# monoblink_wifi_v2.net
KiCad netlist of a schematic drawn in EAGLE
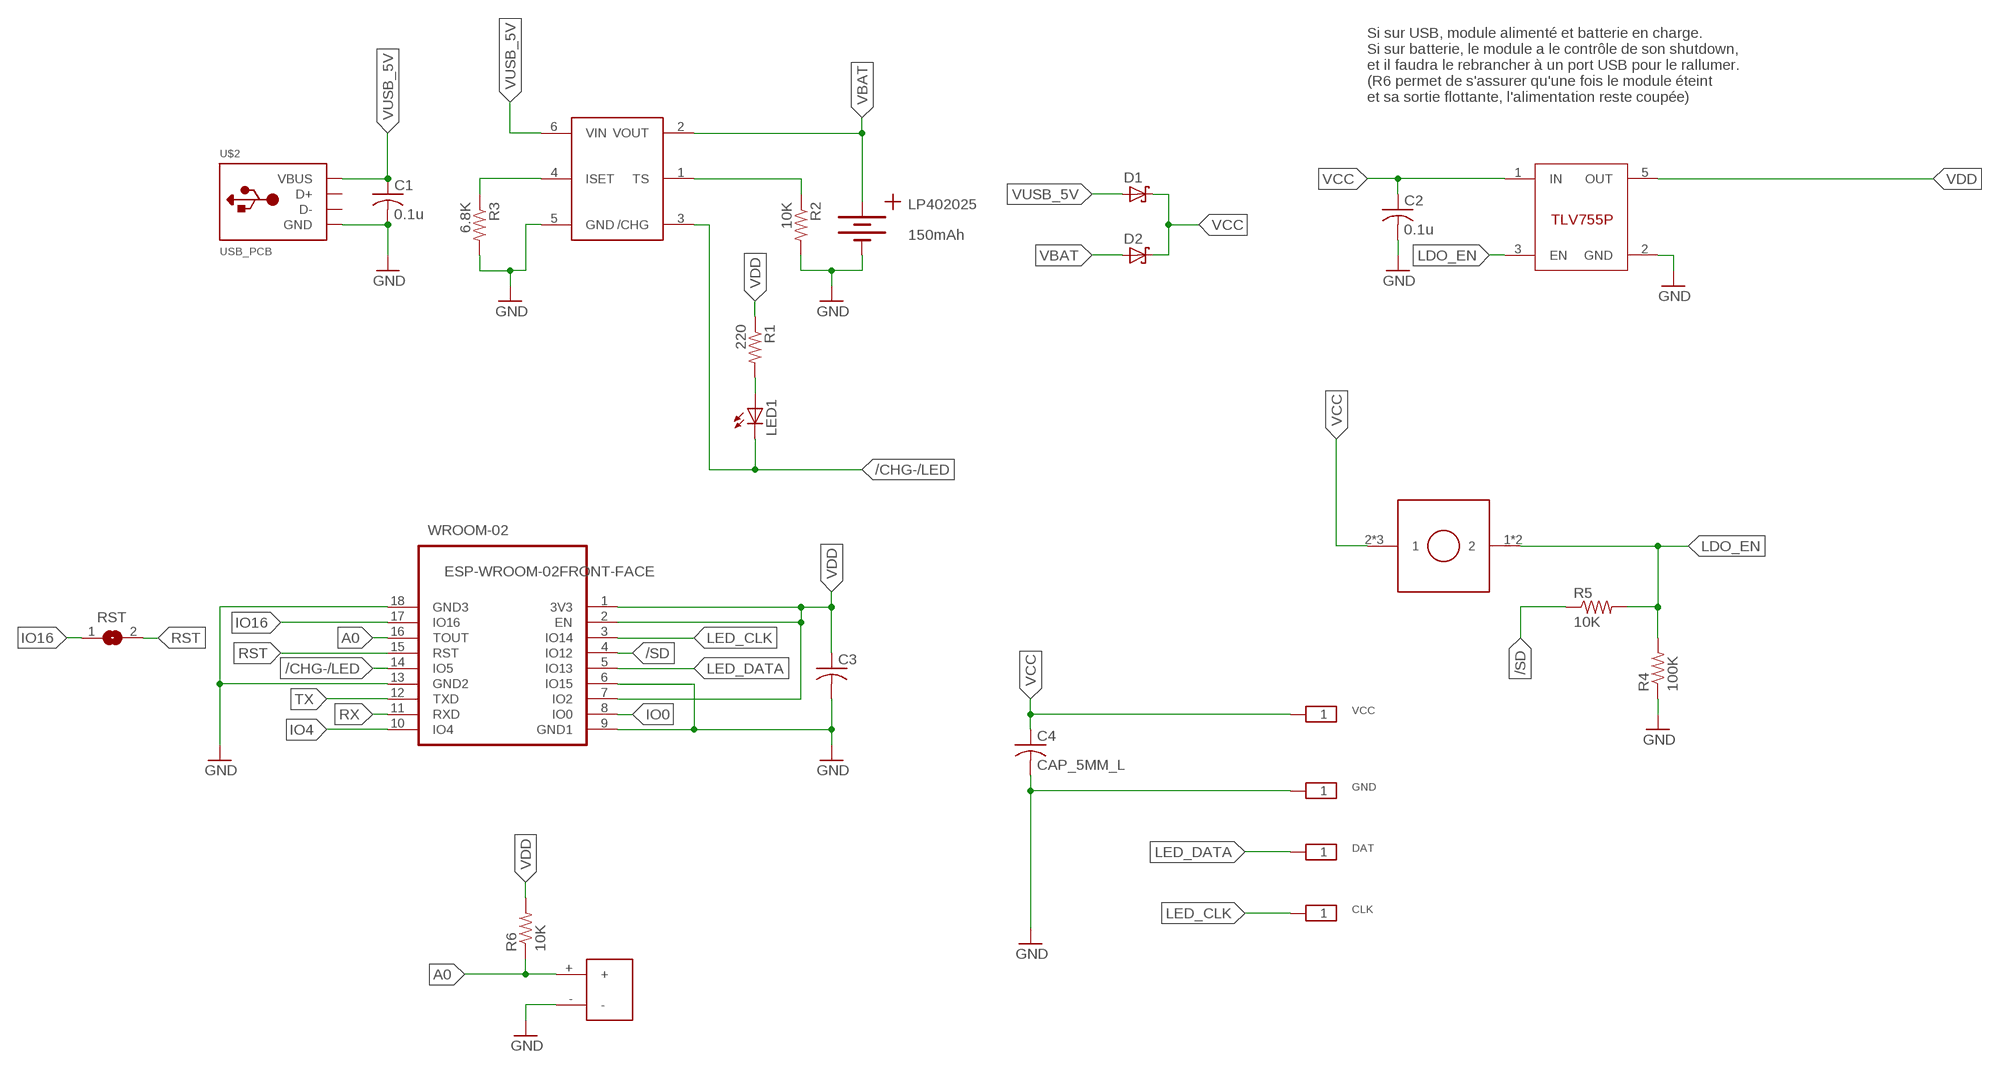
[diagram p0: schematic, sheet 1]

(export (version "E")
  (design (tool "Eeschema 10.0.6"))
  (components
    (comp (ref "C1")
      (value "0.1u")
      (footprint "eagle-import:C0603")
      (libsource (lib "eagle-import") (part "C-USC0603"))
    )
    (comp (ref "C2")
      (value "0.1u")
      (footprint "eagle-import:C0603")
      (libsource (lib "eagle-import") (part "C-USC0603"))
    )
    (comp (ref "C3")
      (value "C-USC0603")
      (footprint "eagle-import:C0603")
      (libsource (lib "eagle-import") (part "C-USC0603"))
    )
    (comp (ref "C4")
      (value "CAP_5MM_L")
      (footprint "eagle-import:TT2D5L")
      (libsource (lib "eagle-import") (part "CAP_5MM_L"))
    )
    (comp (ref "CHG")
      (value "BQ21040")
      (footprint "eagle-import:SOT23-6")
      (libsource (lib "eagle-import") (part "BQ21040"))
    )
    (comp (ref "CLK")
      (value "TESTPAD_PROGSPRING_PIN")
      (footprint "eagle-import:MATRIX_CONN")
      (libsource (lib "eagle-import") (part "TESTPAD_PROGSPRING_PIN"))
    )
    (comp (ref "D1")
      (value "NSR0320MW2T1G")
      (footprint "eagle-import:SOD323")
      (libsource (lib "eagle-import") (part "NSR0320MW2T1G"))
    )
    (comp (ref "D2")
      (value "NSR0320MW2T1G")
      (footprint "eagle-import:SOD323")
      (libsource (lib "eagle-import") (part "NSR0320MW2T1G"))
    )
    (comp (ref "DAT")
      (value "TESTPAD_PROGSPRING_PIN")
      (footprint "eagle-import:MATRIX_CONN")
      (libsource (lib "eagle-import") (part "TESTPAD_PROGSPRING_PIN"))
    )
    (comp (ref "GND")
      (value "TESTPAD_PROGSPRING_PIN")
      (footprint "eagle-import:MATRIX_CONN")
      (libsource (lib "eagle-import") (part "TESTPAD_PROGSPRING_PIN"))
    )
    (comp (ref "LDO")
      (value "TLV755P")
      (footprint "eagle-import:SOT23-5")
      (libsource (lib "eagle-import") (part "TLV755P"))
    )
    (comp (ref "LED1")
      (value "LEDCHIP-LED0603")
      (footprint "eagle-import:CHIP-LED0603")
      (libsource (lib "eagle-import") (part "LEDCHIP-LED0603"))
    )
    (comp (ref "LP402025")
      (value "150mAh")
      (footprint "eagle-import:BATT_CON")
      (libsource (lib "eagle-import") (part "BATT"))
    )
    (comp (ref "ON/OFF")
      (value "KMS231GPLFSNO_PEGS")
      (footprint "eagle-import:KMS231GLFS")
      (libsource (lib "eagle-import") (part "KMS231GPLFSNO_PEGS"))
    )
    (comp (ref "R1")
      (value "220")
      (footprint "eagle-import:R0603")
      (libsource (lib "eagle-import") (part "R-US_R0603"))
    )
    (comp (ref "R2")
      (value "10K")
      (footprint "eagle-import:R0603")
      (libsource (lib "eagle-import") (part "R-US_R0603"))
    )
    (comp (ref "R3")
      (value "6.8K")
      (footprint "eagle-import:R0603")
      (libsource (lib "eagle-import") (part "R-US_R0603"))
    )
    (comp (ref "R4")
      (value "100K")
      (footprint "eagle-import:R0603")
      (libsource (lib "eagle-import") (part "R-US_R0603"))
    )
    (comp (ref "R5")
      (value "10K")
      (footprint "eagle-import:R0603")
      (libsource (lib "eagle-import") (part "R-US_R0603"))
    )
    (comp (ref "R6")
      (value "10K")
      (footprint "eagle-import:R0603")
      (libsource (lib "eagle-import") (part "R-US_R0603"))
    )
    (comp (ref "RST")
      (value "SOLDERJUMPER")
      (footprint "eagle-import:SOLDERJUMPER_ARROW_NOPASTE")
      (libsource (lib "eagle-import") (part "SOLDERJUMPER"))
    )
    (comp (ref "U$1")
      (value "2PIN_STD")
      (footprint "eagle-import:2PIN_STD")
      (libsource (lib "eagle-import") (part "2PIN_STD"))
    )
    (comp (ref "U$2")
      (value "USB_PCB")
      (footprint "eagle-import:USB_PADS")
      (libsource (lib "eagle-import") (part "USB_PCB"))
    )
    (comp (ref "VCC")
      (value "TESTPAD_PROGSPRING_PIN")
      (footprint "eagle-import:MATRIX_CONN")
      (libsource (lib "eagle-import") (part "TESTPAD_PROGSPRING_PIN"))
    )
    (comp (ref "WROOM-02")
      (value "ESP-WROOM-02FRONT-FACE")
      (footprint "eagle-import:FRONT-FACE")
      (libsource (lib "eagle-import") (part "ESP-WROOM-02FRONT-FACE"))
    )
  )
  (nets
    (net (code "1") (name "A0") (class "Default")
      (node (ref "R6") (pin "1") (pinfunction "1_1") (pintype "passive"))
      (node (ref "U$1") (pin "+") (pinfunction "+_+") (pintype "bidirectional"))
      (node (ref "WROOM-02") (pin "16") (pinfunction "TOUT_16") (pintype "bidirectional"))
    )
    (net (code "2") (name "GND") (class "Default")
      (node (ref "C1") (pin "2") (pinfunction "2_2") (pintype "passive"))
      (node (ref "C2") (pin "2") (pinfunction "2_2") (pintype "passive"))
      (node (ref "C3") (pin "2") (pinfunction "2_2") (pintype "passive"))
      (node (ref "C4") (pin "-") (pinfunction "2_-") (pintype "passive"))
      (node (ref "CHG") (pin "5") (pinfunction "GND_5") (pintype "bidirectional"))
      (node (ref "GND") (pin "1") (pinfunction "1_1") (pintype "bidirectional"))
      (node (ref "LDO") (pin "2") (pinfunction "GND_2") (pintype "bidirectional"))
      (node (ref "LP402025") (pin "V-") (pinfunction "-_V-") (pintype "power_in"))
      (node (ref "R2") (pin "2") (pinfunction "2_2") (pintype "passive"))
      (node (ref "R3") (pin "2") (pinfunction "2_2") (pintype "passive"))
      (node (ref "R4") (pin "1") (pinfunction "1_1") (pintype "passive"))
      (node (ref "U$1") (pin "-") (pinfunction "-_-") (pintype "bidirectional"))
      (node (ref "U$2") (pin "GND") (pinfunction "GND_GND") (pintype "power_in"))
      (node (ref "WROOM-02") (pin "13") (pinfunction "GND2_13") (pintype "power_in"))
      (node (ref "WROOM-02") (pin "18") (pinfunction "GND3_18") (pintype "power_in"))
      (node (ref "WROOM-02") (pin "6") (pinfunction "IO15_6") (pintype "bidirectional"))
      (node (ref "WROOM-02") (pin "9") (pinfunction "GND1_9") (pintype "power_in"))
    )
    (net (code "3") (name "IO0") (class "Default")
      (node (ref "WROOM-02") (pin "8") (pinfunction "IO0_8") (pintype "bidirectional"))
    )
    (net (code "4") (name "IO4") (class "Default")
      (node (ref "WROOM-02") (pin "10") (pinfunction "IO4_10") (pintype "bidirectional"))
    )
    (net (code "5") (name "IO16") (class "Default")
      (node (ref "RST") (pin "1") (pinfunction "1_1") (pintype "passive"))
      (node (ref "WROOM-02") (pin "17") (pinfunction "IO16_17") (pintype "bidirectional"))
    )
    (net (code "6") (name "LDO_EN") (class "Default")
      (node (ref "LDO") (pin "3") (pinfunction "EN_3") (pintype "bidirectional"))
      (node (ref "ON/OFF") (pin "1") (pinfunction "2_1") (pintype "bidirectional"))
      (node (ref "ON/OFF") (pin "5") (pinfunction "2_5") (pintype "bidirectional"))
      (node (ref "R4") (pin "2") (pinfunction "2_2") (pintype "passive"))
      (node (ref "R5") (pin "2") (pinfunction "2_2") (pintype "passive"))
    )
    (net (code "7") (name "LED_CLK") (class "Default")
      (node (ref "CLK") (pin "1") (pinfunction "1_1") (pintype "bidirectional"))
      (node (ref "WROOM-02") (pin "3") (pinfunction "IO14_3") (pintype "bidirectional"))
    )
    (net (code "8") (name "LED_DATA") (class "Default")
      (node (ref "DAT") (pin "1") (pinfunction "1_1") (pintype "bidirectional"))
      (node (ref "WROOM-02") (pin "5") (pinfunction "IO13_5") (pintype "bidirectional"))
    )
    (net (code "9") (name "Net-(CHG-ISET)") (class "Default")
      (node (ref "CHG") (pin "4") (pinfunction "ISET_4") (pintype "bidirectional"))
      (node (ref "R3") (pin "1") (pinfunction "1_1") (pintype "passive"))
    )
    (net (code "10") (name "Net-(CHG-TS)") (class "Default")
      (node (ref "CHG") (pin "1") (pinfunction "TS_1") (pintype "bidirectional"))
      (node (ref "R2") (pin "1") (pinfunction "1_1") (pintype "passive"))
    )
    (net (code "11") (name "Net-(LED1-PadA)") (class "Default")
      (node (ref "LED1") (pin "A") (pinfunction "A_A") (pintype "passive"))
      (node (ref "R1") (pin "2") (pinfunction "2_2") (pintype "passive"))
    )
    (net (code "12") (name "RST") (class "Default")
      (node (ref "RST") (pin "2") (pinfunction "2_2") (pintype "passive"))
      (node (ref "WROOM-02") (pin "15") (pinfunction "RST_15") (pintype "bidirectional"))
    )
    (net (code "13") (name "RX") (class "Default")
      (node (ref "WROOM-02") (pin "11") (pinfunction "RXD_11") (pintype "bidirectional"))
    )
    (net (code "14") (name "TX") (class "Default")
      (node (ref "WROOM-02") (pin "12") (pinfunction "TXD_12") (pintype "bidirectional"))
    )
    (net (code "15") (name "VBAT") (class "Default")
      (node (ref "CHG") (pin "2") (pinfunction "VOUT_2") (pintype "bidirectional"))
      (node (ref "D2") (pin "2") (pinfunction "A_2") (pintype "passive"))
      (node (ref "LP402025") (pin "V+") (pinfunction "+_V+") (pintype "power_in"))
    )
    (net (code "16") (name "VCC") (class "Default")
      (node (ref "C2") (pin "1") (pinfunction "1_1") (pintype "passive"))
      (node (ref "C4") (pin "+") (pinfunction "1_+") (pintype "passive"))
      (node (ref "D1") (pin "1") (pinfunction "C_1") (pintype "passive"))
      (node (ref "D2") (pin "1") (pinfunction "C_1") (pintype "passive"))
      (node (ref "LDO") (pin "1") (pinfunction "IN_1") (pintype "bidirectional"))
      (node (ref "ON/OFF") (pin "2") (pinfunction "1_2") (pintype "bidirectional"))
      (node (ref "ON/OFF") (pin "3") (pinfunction "1_3") (pintype "bidirectional"))
      (node (ref "ON/OFF") (pin "4") (pinfunction "1_4") (pintype "bidirectional"))
      (node (ref "VCC") (pin "1") (pinfunction "1_1") (pintype "bidirectional"))
    )
    (net (code "17") (name "VDD") (class "Default")
      (node (ref "C3") (pin "1") (pinfunction "1_1") (pintype "passive"))
      (node (ref "LDO") (pin "5") (pinfunction "OUT_5") (pintype "bidirectional"))
      (node (ref "R1") (pin "1") (pinfunction "1_1") (pintype "passive"))
      (node (ref "R6") (pin "2") (pinfunction "2_2") (pintype "passive"))
      (node (ref "WROOM-02") (pin "1") (pinfunction "3V3_1") (pintype "power_in"))
      (node (ref "WROOM-02") (pin "2") (pinfunction "EN_2") (pintype "bidirectional"))
      (node (ref "WROOM-02") (pin "7") (pinfunction "IO2_7") (pintype "bidirectional"))
    )
    (net (code "18") (name "VUSB_5V") (class "Default")
      (node (ref "C1") (pin "1") (pinfunction "1_1") (pintype "passive"))
      (node (ref "CHG") (pin "6") (pinfunction "VIN_6") (pintype "bidirectional"))
      (node (ref "D1") (pin "2") (pinfunction "A_2") (pintype "passive"))
      (node (ref "U$2") (pin "V_SUPPLY") (pinfunction "VBUS_V_SUPPLY") (pintype "power_in"))
    )
    (net (code "19") (name "unconnected-(U$2-PadD+)") (class "Default")
      (node (ref "U$2") (pin "D+") (pinfunction "D+_D+") (pintype "bidirectional"))
    )
    (net (code "20") (name "unconnected-(U$2-PadD-)") (class "Default")
      (node (ref "U$2") (pin "D-") (pinfunction "D-_D-") (pintype "bidirectional"))
    )
    (net (code "21") (name "{slash}CHG-{slash}LED") (class "Default")
      (node (ref "CHG") (pin "3") (pinfunction "/CHG_3") (pintype "bidirectional"))
      (node (ref "LED1") (pin "C") (pinfunction "C_C") (pintype "passive"))
      (node (ref "WROOM-02") (pin "14") (pinfunction "IO5_14") (pintype "open_collector"))
    )
    (net (code "22") (name "{slash}SD") (class "Default")
      (node (ref "R5") (pin "1") (pinfunction "1_1") (pintype "passive"))
      (node (ref "WROOM-02") (pin "4") (pinfunction "IO12_4") (pintype "bidirectional"))
    )
  )
)
